# main.net
KiCad netlist of a schematic drawn in Altium Designer
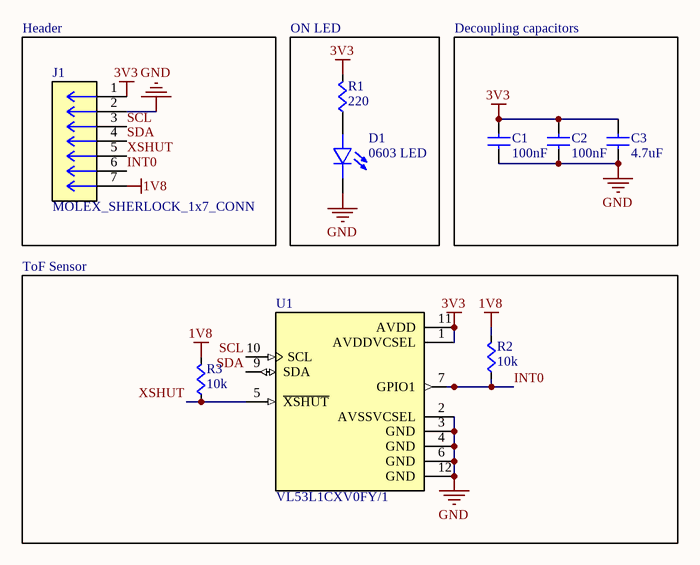
[diagram p0: main.SchDoc]

(export (version "E")
  (design (tool "Eeschema 10.0.6"))
  (components
    (comp (ref "C1")
      (value "100nF")
      (footprint "CAPC0603")
      (fields (field (name "Comment") "Cap"))
      (libsource (lib "Passives") (part "Cap"))
    )
    (comp (ref "C2")
      (value "100nF")
      (footprint "CAPC0603")
      (fields (field (name "Comment") "Cap"))
      (libsource (lib "Passives") (part "Cap"))
    )
    (comp (ref "C3")
      (value "4.7uF")
      (footprint "CAPC0603")
      (fields (field (name "Comment") "Cap"))
      (libsource (lib "Passives") (part "Cap"))
    )
    (comp (ref "D1")
      (value "0603 LED")
      (footprint "0603 (LED)")
      (description "150060SS75000 ¦ LED Indication - Discrete 1.9V 0603 (1608 Metric)")
      (libsource (lib "Alexandria") (part "0603 LED"))
    )
    (comp (ref "J1")
      (value "MOLEX_SHERLOCK_1x7_CONN")
      (footprint "CON_353620750")
      (description "1x7 2mm pitch sherlock connector")
      (fields (field (name "MP") "353620750"))
      (libsource (lib "353620750") (part "MOLEX_SHERLOCK_1x7_CONN"))
    )
    (comp (ref "R1")
      (value "220")
      (footprint "RES0603")
      (description "SMD, RES0603")
      (fields (field (name "Comment") "Res"))
      (libsource (lib "Passives") (part "Res"))
    )
    (comp (ref "R2")
      (value "10k")
      (footprint "RES0603")
      (description "SMD, RES0603")
      (fields (field (name "Comment") "Res"))
      (libsource (lib "Passives") (part "Res"))
    )
    (comp (ref "R3")
      (value "10k")
      (footprint "RES0603")
      (description "SMD, RES0603")
      (fields (field (name "Comment") "Res"))
      (libsource (lib "Passives") (part "Res"))
    )
    (comp (ref "U1")
      (value "VL53L1CXV0FY/1")
      (footprint "LGA-12 (VL53L1CXV0FY/1)")
      (description "ToF Optical Sensor 157.480 (4m) I²C Output from STMelectronics")
      (fields (field (name "MF") "STMicroelectronics"))
      (libsource (lib "Alexandria") (part "VL53L1CXV0FY/1"))
    )
  )
  (nets
    (net (code "1") (name "/INT0") (class "Default")
      (node (ref "J1") (pin "6") (pinfunction "6_6") (pintype "passive"))
      (node (ref "R2") (pin "2") (pinfunction "B_2") (pintype "passive"))
      (node (ref "U1") (pin "7") (pinfunction "GPIO1_7") (pintype "output"))
    )
    (net (code "2") (name "/SCL") (class "Default")
      (node (ref "J1") (pin "3") (pinfunction "3_3") (pintype "passive"))
      (node (ref "U1") (pin "10") (pinfunction "SCL_10") (pintype "input"))
    )
    (net (code "3") (name "/SDA") (class "Default")
      (node (ref "J1") (pin "4") (pinfunction "4_4") (pintype "passive"))
      (node (ref "U1") (pin "9") (pinfunction "SDA_9") (pintype "bidirectional"))
    )
    (net (code "4") (name "/XSHUT") (class "Default")
      (node (ref "J1") (pin "5") (pinfunction "5_5") (pintype "passive"))
      (node (ref "R3") (pin "2") (pinfunction "B_2") (pintype "passive"))
      (node (ref "U1") (pin "5") (pinfunction "~{XSHUT}_5") (pintype "input"))
    )
    (net (code "5") (name "1V8") (class "Default")
      (node (ref "J1") (pin "7") (pinfunction "7_7") (pintype "passive"))
      (node (ref "R2") (pin "1") (pinfunction "A_1") (pintype "passive"))
      (node (ref "R3") (pin "1") (pinfunction "A_1") (pintype "passive"))
    )
    (net (code "6") (name "3V3") (class "Default")
      (node (ref "C1") (pin "1") (pinfunction "A_1") (pintype "passive"))
      (node (ref "C2") (pin "1") (pinfunction "A_1") (pintype "passive"))
      (node (ref "C3") (pin "1") (pinfunction "A_1") (pintype "passive"))
      (node (ref "J1") (pin "1") (pinfunction "1_1") (pintype "passive"))
      (node (ref "R1") (pin "1") (pinfunction "A_1") (pintype "passive"))
      (node (ref "U1") (pin "1") (pinfunction "AVDDVCSEL_1") (pintype "power_in"))
      (node (ref "U1") (pin "11") (pinfunction "AVDD_11") (pintype "power_in"))
    )
    (net (code "7") (name "GND") (class "Default")
      (node (ref "C1") (pin "2") (pinfunction "B_2") (pintype "passive"))
      (node (ref "C2") (pin "2") (pinfunction "B_2") (pintype "passive"))
      (node (ref "C3") (pin "2") (pinfunction "B_2") (pintype "passive"))
      (node (ref "D1") (pin "C") (pinfunction "C_C") (pintype "passive"))
      (node (ref "J1") (pin "2") (pinfunction "2_2") (pintype "passive"))
      (node (ref "U1") (pin "12") (pinfunction "GND_12") (pintype "power_in"))
      (node (ref "U1") (pin "2") (pinfunction "AVSSVCSEL_2") (pintype "power_in"))
      (node (ref "U1") (pin "3") (pinfunction "GND_3") (pintype "power_in"))
      (node (ref "U1") (pin "4") (pinfunction "GND_4") (pintype "power_in"))
      (node (ref "U1") (pin "6") (pinfunction "GND_6") (pintype "power_in"))
    )
    (net (code "8") (name "Net-(R1-B)") (class "Default")
      (node (ref "D1") (pin "A") (pinfunction "A_A") (pintype "passive"))
      (node (ref "R1") (pin "2") (pinfunction "B_2") (pintype "passive"))
    )
  )
)
